# Headphone-Amplifier-ClassAB-alt4.net
KiCad netlist of a schematic drawn in EAGLE
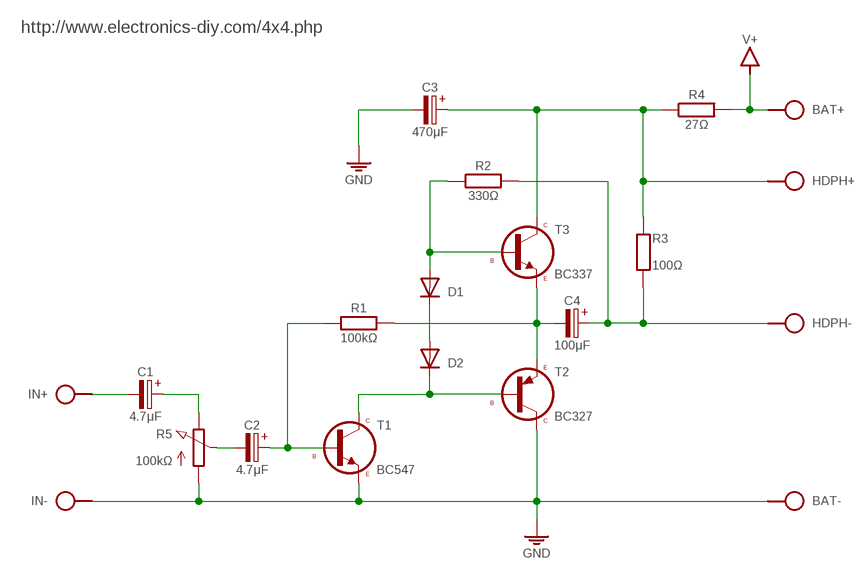
[diagram p0: schematic, sheet 1]

(export (version "E")
  (design (tool "Eeschema 10.0.6"))
  (components
    (comp (ref "BAT")
      (value "SPAD+-+-")
      (footprint "eagle-import:SPAD+-")
      (libsource (lib "eagle-import") (part "SPAD+-+-"))
    )
    (comp (ref "C1")
      (value "4.7μF")
      (footprint "eagle-import:E2,5-4")
      (libsource (lib "eagle-import") (part "CPOLE2,5-4"))
    )
    (comp (ref "C2")
      (value "4.7μF")
      (footprint "eagle-import:E2,5-4")
      (libsource (lib "eagle-import") (part "CPOLE2,5-4"))
    )
    (comp (ref "C3")
      (value "470μF")
      (footprint "eagle-import:E5-6")
      (libsource (lib "eagle-import") (part "CPOLE5-6"))
    )
    (comp (ref "C4")
      (value "100μF")
      (footprint "eagle-import:E5-4")
      (libsource (lib "eagle-import") (part "CPOLE5-4"))
    )
    (comp (ref "D1")
      (value "1N414834-5V")
      (footprint "eagle-import:DO34-5V")
      (libsource (lib "eagle-import") (part "1N414834-5V"))
    )
    (comp (ref "D2")
      (value "1N414834-5V")
      (footprint "eagle-import:DO34-5V")
      (libsource (lib "eagle-import") (part "1N414834-5V"))
    )
    (comp (ref "HDPH")
      (value "SPAD+--+")
      (footprint "eagle-import:SPAD-+")
      (libsource (lib "eagle-import") (part "SPAD+--+"))
    )
    (comp (ref "IN")
      (value "SPAD+--+")
      (footprint "eagle-import:SPAD-+")
      (libsource (lib "eagle-import") (part "SPAD+--+"))
    )
    (comp (ref "R1")
      (value "100kΩ")
      (footprint "eagle-import:0202_7")
      (libsource (lib "eagle-import") (part "R-H0202/7"))
    )
    (comp (ref "R2")
      (value "330Ω")
      (footprint "eagle-import:0202_7")
      (libsource (lib "eagle-import") (part "R-H0202/7"))
    )
    (comp (ref "R3")
      (value "100Ω")
      (footprint "eagle-import:0202_7")
      (libsource (lib "eagle-import") (part "R0202/7"))
    )
    (comp (ref "R4")
      (value "27Ω")
      (footprint "eagle-import:0204V")
      (libsource (lib "eagle-import") (part "R-H-V-X"))
    )
    (comp (ref "R5")
      (value "100kΩ")
      (footprint "eagle-import:CONN-3P")
      (libsource (lib "eagle-import") (part "POT-3P"))
    )
    (comp (ref "T1")
      (value "BC547")
      (footprint "eagle-import:TO92")
      (libsource (lib "eagle-import") (part "BC547"))
    )
    (comp (ref "T2")
      (value "BC327")
      (footprint "eagle-import:TO92")
      (libsource (lib "eagle-import") (part "BC327"))
    )
    (comp (ref "T3")
      (value "BC337")
      (footprint "eagle-import:TO92-CBE")
      (libsource (lib "eagle-import") (part "BC337CBE"))
    )
  )
  (nets
    (net (code "1") (name "GND") (class "Default")
      (node (ref "BAT") (pin "1") (pinfunction "P$1_1") (pintype "passive"))
      (node (ref "C3") (pin "-") (pinfunction "-_-") (pintype "passive"))
      (node (ref "IN") (pin "1") (pinfunction "P$1_1") (pintype "passive"))
      (node (ref "R5") (pin "1") (pinfunction "A_1") (pintype "passive"))
      (node (ref "T1") (pin "3") (pinfunction "E_3") (pintype "passive"))
      (node (ref "T2") (pin "1") (pinfunction "C_1") (pintype "passive"))
    )
    (net (code "2") (name "Net-(D1-PadC)") (class "Default")
      (node (ref "D1") (pin "C") (pinfunction "C_C") (pintype "passive"))
      (node (ref "D2") (pin "A") (pinfunction "A_A") (pintype "passive"))
    )
    (net (code "3") (name "Net-(HDPHA-P$1)") (class "Default")
      (node (ref "C3") (pin "+") (pinfunction "+_+") (pintype "passive"))
      (node (ref "HDPH") (pin "2") (pinfunction "P$1_2") (pintype "passive"))
      (node (ref "R3") (pin "2") (pinfunction "1_2") (pintype "passive"))
      (node (ref "R4") (pin "2") (pinfunction "1_2") (pintype "passive"))
      (node (ref "T3") (pin "1") (pinfunction "C_1") (pintype "passive"))
    )
    (net (code "4") (name "Net-(HDPHB-P$1)") (class "Default")
      (node (ref "C4") (pin "+") (pinfunction "+_+") (pintype "passive"))
      (node (ref "HDPH") (pin "1") (pinfunction "P$1_1") (pintype "passive"))
      (node (ref "R2") (pin "2") (pinfunction "2_2") (pintype "passive"))
      (node (ref "R3") (pin "1") (pinfunction "2_1") (pintype "passive"))
    )
    (net (code "5") (name "Net-(INA-P$1)") (class "Default")
      (node (ref "C1") (pin "-") (pinfunction "-_-") (pintype "passive"))
      (node (ref "IN") (pin "2") (pinfunction "P$1_2") (pintype "passive"))
    )
    (net (code "6") (name "Net-(R5-E)") (class "Default")
      (node (ref "C1") (pin "+") (pinfunction "+_+") (pintype "passive"))
      (node (ref "R5") (pin "3") (pinfunction "E_3") (pintype "passive"))
    )
    (net (code "7") (name "Net-(R5-S)") (class "Default")
      (node (ref "C2") (pin "-") (pinfunction "-_-") (pintype "passive"))
      (node (ref "R5") (pin "2") (pinfunction "S_2") (pintype "passive"))
    )
    (net (code "8") (name "Net-(T1-B)") (class "Default")
      (node (ref "C2") (pin "+") (pinfunction "+_+") (pintype "passive"))
      (node (ref "R1") (pin "1") (pinfunction "1_1") (pintype "passive"))
      (node (ref "T1") (pin "2") (pinfunction "B_2") (pintype "passive"))
    )
    (net (code "9") (name "Net-(T1-C)") (class "Default")
      (node (ref "D2") (pin "C") (pinfunction "C_C") (pintype "passive"))
      (node (ref "T1") (pin "1") (pinfunction "C_1") (pintype "passive"))
      (node (ref "T2") (pin "2") (pinfunction "B_2") (pintype "passive"))
    )
    (net (code "10") (name "Net-(T2-E)") (class "Default")
      (node (ref "C4") (pin "-") (pinfunction "-_-") (pintype "passive"))
      (node (ref "R1") (pin "2") (pinfunction "2_2") (pintype "passive"))
      (node (ref "T2") (pin "3") (pinfunction "E_3") (pintype "passive"))
      (node (ref "T3") (pin "3") (pinfunction "E_3") (pintype "passive"))
    )
    (net (code "11") (name "Net-(T3-B)") (class "Default")
      (node (ref "D1") (pin "A") (pinfunction "A_A") (pintype "passive"))
      (node (ref "R2") (pin "1") (pinfunction "1_1") (pintype "passive"))
      (node (ref "T3") (pin "2") (pinfunction "B_2") (pintype "passive"))
    )
    (net (code "12") (name "V+") (class "Default")
      (node (ref "BAT") (pin "2") (pinfunction "P$1_2") (pintype "passive"))
      (node (ref "R4") (pin "1") (pinfunction "2_1") (pintype "passive"))
    )
  )
)
